# Sensor_template.net
KiCad netlist of a schematic drawn in Altium Designer
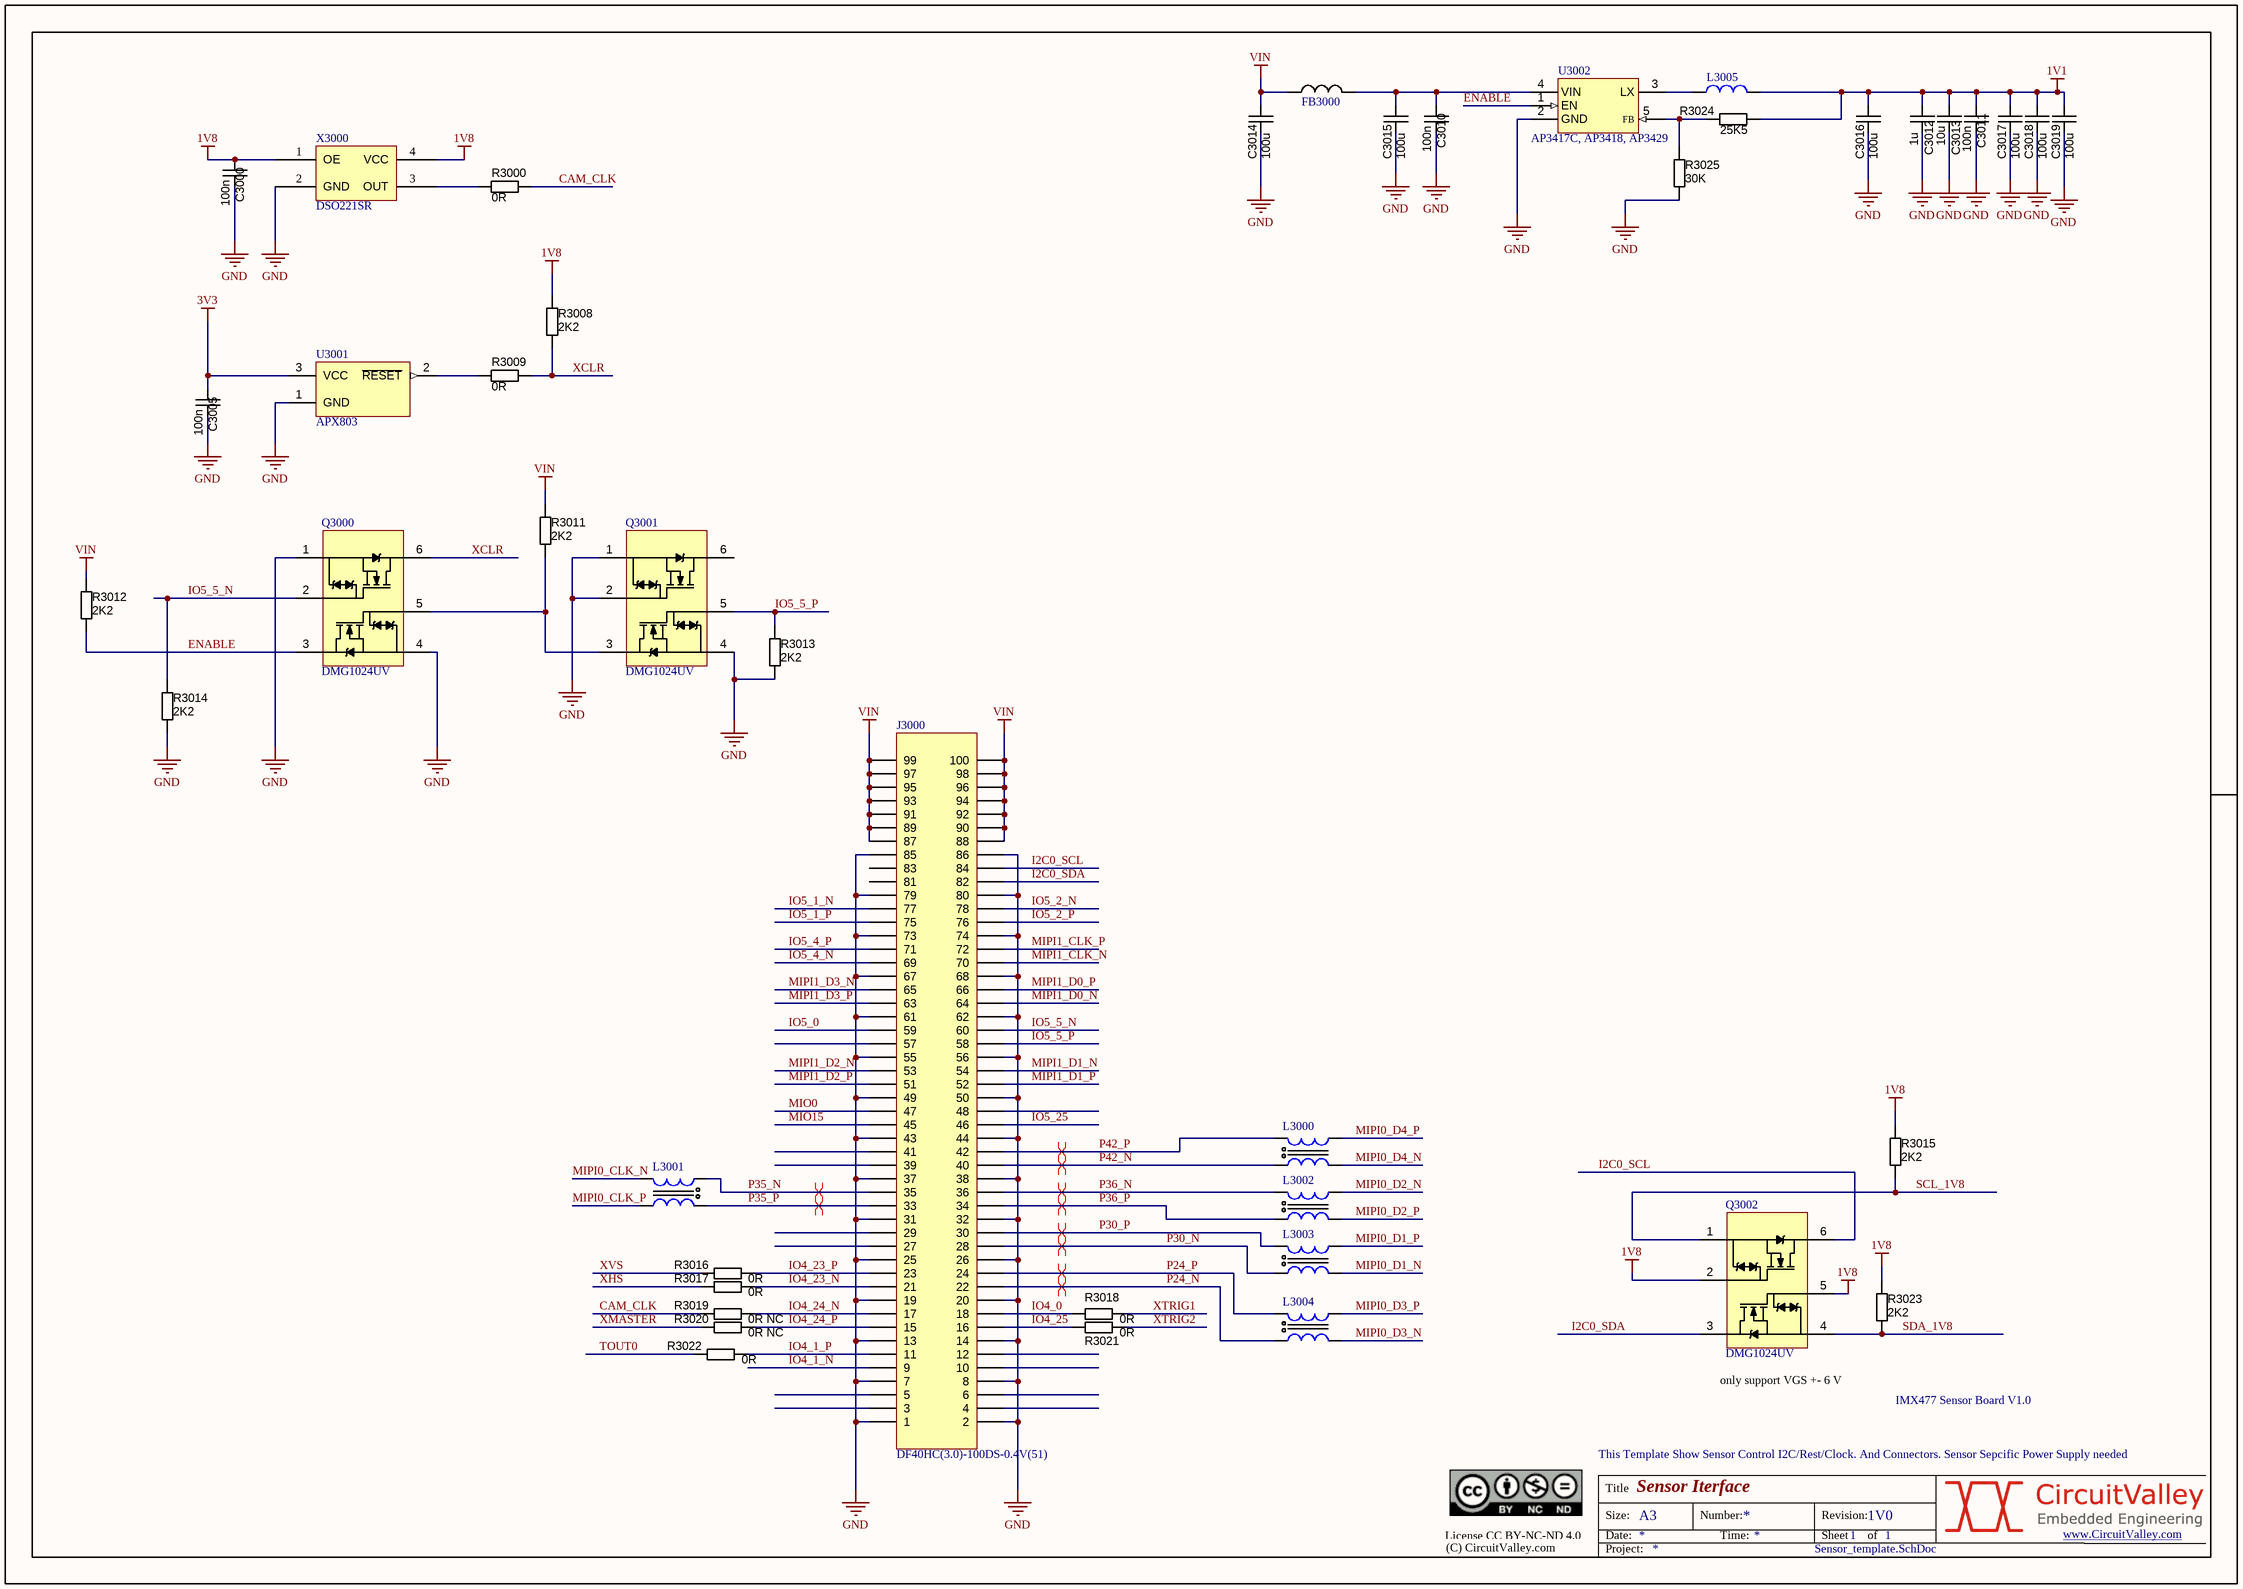
[diagram p0: Sensor_template.SchDoc]

(export (version "E")
  (design (tool "Eeschema 10.0.6"))
  (components
    (comp (ref "C3000")
      (value "100n")
      (footprint "CAPC1005N")
      (description "Capacitor SMD Cer 10nF 10% 16V X7R 0402")
      (fields (field (name "TOLERANCE") "±10%"))
      (libsource (lib "PBL - Capacitors") (part "CAPC_10n_0402_16V_10%"))
    )
    (comp (ref "C3005")
      (value "100n")
      (footprint "CAPC1005N")
      (description "Capacitor SMD Cer 10nF 10% 16V X7R 0402")
      (fields (field (name "TOLERANCE") "±10%"))
      (libsource (lib "PBL - Capacitors") (part "CAPC_10n_0402_16V_10%"))
    )
    (comp (ref "C3010")
      (value "100n")
      (footprint "CAPC1005N")
      (description "Capacitor SMD Cer 10nF 10% 16V X7R 0402")
      (fields (field (name "TOLERANCE") "±10%"))
      (libsource (lib "PBL - Capacitors") (part "CAPC_10n_0402_16V_10%"))
    )
    (comp (ref "C3011")
      (value "100n")
      (footprint "CAPC1005N")
      (description "Capacitor SMD Cer 10nF 10% 16V X7R 0402")
      (fields (field (name "TOLERANCE") "±10%"))
      (libsource (lib "PBL - Capacitors") (part "CAPC_10n_0402_16V_10%"))
    )
    (comp (ref "C3012")
      (value "1u")
      (footprint "CAPC1608N")
      (description "Capacitor SMD Cer 560pF 5% 50V NP0 0603")
      (fields (field (name "Comment") "approved sub OK"))
      (libsource (lib "PBL - Capacitors") (part "CAPC_560p_0603_5%"))
    )
    (comp (ref "C3013")
      (value "10u")
      (footprint "CAPC1608N")
      (description "Capacitor SMD Cer 560pF 5% 50V NP0 0603")
      (fields (field (name "Comment") "approved sub OK"))
      (libsource (lib "PBL - Capacitors") (part "CAPC_560p_0603_5%"))
    )
    (comp (ref "C3014")
      (value "100u")
      (footprint "CAPC2012N")
      (description "Capacitor SMD Cer 1uF 10% 16V X7R 0805")
      (fields (field (name "TOLERANCE") "±10%") (field (name "Comment") "approved sub OK"))
      (libsource (lib "PBL - Capacitors") (part "CAPC_1u_0805"))
    )
    (comp (ref "C3015")
      (value "100u")
      (footprint "CAPC2012N")
      (description "Capacitor SMD Cer 1uF 10% 16V X7R 0805")
      (fields (field (name "TOLERANCE") "±10%") (field (name "Comment") "approved sub OK"))
      (libsource (lib "PBL - Capacitors") (part "CAPC_1u_0805"))
    )
    (comp (ref "C3016")
      (value "100u")
      (footprint "CAPC2012N")
      (description "Capacitor SMD Cer 1uF 10% 16V X7R 0805")
      (fields (field (name "TOLERANCE") "±10%") (field (name "Comment") "approved sub OK"))
      (libsource (lib "PBL - Capacitors") (part "CAPC_1u_0805"))
    )
    (comp (ref "C3017")
      (value "100u")
      (footprint "CAPC2012N")
      (description "Capacitor SMD Cer 1uF 10% 16V X7R 0805")
      (fields (field (name "TOLERANCE") "±10%") (field (name "Comment") "approved sub OK"))
      (libsource (lib "PBL - Capacitors") (part "CAPC_1u_0805"))
    )
    (comp (ref "C3018")
      (value "100u")
      (footprint "CAPC2012N")
      (description "Capacitor SMD Cer 1uF 10% 16V X7R 0805")
      (fields (field (name "TOLERANCE") "±10%") (field (name "Comment") "approved sub OK"))
      (libsource (lib "PBL - Capacitors") (part "CAPC_1u_0805"))
    )
    (comp (ref "C3019")
      (value "100u")
      (footprint "CAPC2012N")
      (description "Capacitor SMD Cer 1uF 10% 16V X7R 0805")
      (fields (field (name "TOLERANCE") "±10%") (field (name "Comment") "approved sub OK"))
      (libsource (lib "PBL - Capacitors") (part "CAPC_1u_0805"))
    )
    (comp (ref "FB3000") (value "Ferrite") (footprint "INDC1608N") (libsource (lib "cvlib") (part "Ferrite")))
    (comp (ref "J3000")
      (value "DF40HC(3.0)-100DS-0.4V(51)")
      (footprint "DF40HC(3.0)-100DS-0.4V(51)")
      (description "Hiro 100 pin Connector Receptical")
      (libsource (lib "cvlib") (part "DF40HC(3.0)-100DS-0.4V(51)"))
    )
    (comp (ref "L3000")
      (value "DLM11SN900HZ2L")
      (footprint "DLM11SN900HZ2L")
      (libsource (lib "") (part "Choke_1"))
    )
    (comp (ref "L3001")
      (value "DLM11SN900HZ2L")
      (footprint "DLM11SN900HZ2L")
      (libsource (lib "cvlib") (part "Choke"))
    )
    (comp (ref "L3002")
      (value "DLM11SN900HZ2L")
      (footprint "DLM11SN900HZ2L")
      (libsource (lib "") (part "Choke_1"))
    )
    (comp (ref "L3003")
      (value "DLM11SN900HZ2L")
      (footprint "DLM11SN900HZ2L")
      (libsource (lib "") (part "Choke_1"))
    )
    (comp (ref "L3004")
      (value "DLM11SN900HZ2L")
      (footprint "DLM11SN900HZ2L")
      (libsource (lib "cvlib") (part "Choke"))
    )
    (comp (ref "L3005")
      (value "DFE252012P-2R2M=P2")
      (footprint "DFE252012P-2R2M=P2")
      (libsource (lib "cvlib") (part "inductor_smd"))
    )
    (comp (ref "Q3000") (value "DMG1024UV") (footprint "SOT563") (libsource (lib "cvlib") (part "DMG1024UV")))
    (comp (ref "Q3001") (value "DMG1024UV") (footprint "SOT563") (libsource (lib "cvlib") (part "DMG1024UV")))
    (comp (ref "Q3002") (value "DMG1024UV") (footprint "SOT563") (libsource (lib "cvlib") (part "DMG1024UV")))
    (comp (ref "R3000")
      (value "0R")
      (footprint "RESC1005N")
      (description "Resistor SMD chip 3.3k Ohm 0.063W 5% 0402")
      (fields (field (name "TOLERANCE") "±5%") (field (name "Comment") "Thick Film"))
      (libsource (lib "PBL - Resistors") (part "RES_3K3_0402_5%"))
    )
    (comp (ref "R3008")
      (value "2K2")
      (footprint "RESC1005N")
      (description "Resistor SMD chip 3.3k Ohm 0.063W 5% 0402")
      (fields (field (name "TOLERANCE") "±5%") (field (name "Comment") "Thick Film"))
      (libsource (lib "") (part "RES_3K3_0402_5%_2"))
    )
    (comp (ref "R3009")
      (value "0R")
      (footprint "RESC1005N")
      (description "Resistor SMD chip 3.3k Ohm 0.063W 5% 0402")
      (fields (field (name "TOLERANCE") "±5%") (field (name "Comment") "Thick Film"))
      (libsource (lib "PBL - Resistors") (part "RES_3K3_0402_5%"))
    )
    (comp (ref "R3011")
      (value "2K2")
      (footprint "RESC1005N")
      (description "Resistor SMD chip 3.3k Ohm 0.063W 5% 0402")
      (fields (field (name "TOLERANCE") "±5%") (field (name "Comment") "Thick Film"))
      (libsource (lib "") (part "RES_3K3_0402_5%_1"))
    )
    (comp (ref "R3012")
      (value "2K2")
      (footprint "RESC1005N")
      (description "Resistor SMD chip 3.3k Ohm 0.063W 5% 0402")
      (fields (field (name "TOLERANCE") "±5%") (field (name "Comment") "Thick Film"))
      (libsource (lib "") (part "RES_3K3_0402_5%_2"))
    )
    (comp (ref "R3013")
      (value "2K2")
      (footprint "RESC1005N")
      (description "Resistor SMD chip 3.3k Ohm 0.063W 5% 0402")
      (fields (field (name "TOLERANCE") "±5%") (field (name "Comment") "Thick Film"))
      (libsource (lib "") (part "RES_3K3_0402_5%_1"))
    )
    (comp (ref "R3014")
      (value "2K2")
      (footprint "RESC1005N")
      (description "Resistor SMD chip 3.3k Ohm 0.063W 5% 0402")
      (fields (field (name "TOLERANCE") "±5%") (field (name "Comment") "Thick Film"))
      (libsource (lib "") (part "RES_3K3_0402_5%_2"))
    )
    (comp (ref "R3015")
      (value "2K2")
      (footprint "RESC1005N")
      (description "Resistor SMD chip 3.3k Ohm 0.063W 5% 0402")
      (fields (field (name "TOLERANCE") "±5%") (field (name "Comment") "Thick Film"))
      (libsource (lib "") (part "RES_3K3_0402_5%_1"))
    )
    (comp (ref "R3016")
      (value "0R")
      (footprint "RESC1005N")
      (description "Resistor SMD chip 3.3k Ohm 0.063W 5% 0402")
      (fields (field (name "TOLERANCE") "±5%") (field (name "Comment") "Thick Film"))
      (libsource (lib "PBL - Resistors") (part "RES_3K3_0402_5%"))
    )
    (comp (ref "R3017")
      (value "0R")
      (footprint "RESC1005N")
      (description "Resistor SMD chip 3.3k Ohm 0.063W 5% 0402")
      (fields (field (name "TOLERANCE") "±5%") (field (name "Comment") "Thick Film"))
      (libsource (lib "PBL - Resistors") (part "RES_3K3_0402_5%"))
    )
    (comp (ref "R3018")
      (value "0R")
      (footprint "RESC1005N")
      (description "Resistor SMD chip 3.3k Ohm 0.063W 5% 0402")
      (fields (field (name "TOLERANCE") "±5%") (field (name "Comment") "Thick Film"))
      (libsource (lib "PBL - Resistors") (part "RES_3K3_0402_5%"))
    )
    (comp (ref "R3019")
      (value "0R NC")
      (footprint "RESC1005N")
      (description "Resistor SMD chip 3.3k Ohm 0.063W 5% 0402")
      (fields (field (name "TOLERANCE") "±5%") (field (name "Comment") "Thick Film"))
      (libsource (lib "PBL - Resistors") (part "RES_3K3_0402_5%"))
    )
    (comp (ref "R3020")
      (value "0R NC")
      (footprint "RESC1005N")
      (description "Resistor SMD chip 3.3k Ohm 0.063W 5% 0402")
      (fields (field (name "TOLERANCE") "±5%") (field (name "Comment") "Thick Film"))
      (libsource (lib "PBL - Resistors") (part "RES_3K3_0402_5%"))
    )
    (comp (ref "R3021")
      (value "0R")
      (footprint "RESC1005N")
      (description "Resistor SMD chip 3.3k Ohm 0.063W 5% 0402")
      (fields (field (name "TOLERANCE") "±5%") (field (name "Comment") "Thick Film"))
      (libsource (lib "PBL - Resistors") (part "RES_3K3_0402_5%"))
    )
    (comp (ref "R3022")
      (value "0R")
      (footprint "RESC1005N")
      (description "Resistor SMD chip 3.3k Ohm 0.063W 5% 0402")
      (fields (field (name "TOLERANCE") "±5%") (field (name "Comment") "Thick Film"))
      (libsource (lib "PBL - Resistors") (part "RES_3K3_0402_5%"))
    )
    (comp (ref "R3023")
      (value "2K2")
      (footprint "RESC1005N")
      (description "Resistor SMD chip 3.3k Ohm 0.063W 5% 0402")
      (fields (field (name "TOLERANCE") "±5%") (field (name "Comment") "Thick Film"))
      (libsource (lib "") (part "RES_3K3_0402_5%_1"))
    )
    (comp (ref "R3024")
      (value "25K5")
      (footprint "RESC1005N")
      (description "Resistor SMD chip 3.3k Ohm 0.063W 5% 0402")
      (fields (field (name "TOLERANCE") "±5%") (field (name "Comment") "Thick Film"))
      (libsource (lib "") (part "RES_3K3_0402_5%_3"))
    )
    (comp (ref "R3025")
      (value "30K")
      (footprint "RESC1005N")
      (description "Resistor SMD chip 3.3k Ohm 0.063W 5% 0402")
      (fields (field (name "TOLERANCE") "±5%") (field (name "Comment") "Thick Film"))
      (libsource (lib "") (part "RES_3K3_0402_5%_1"))
    )
    (comp (ref "U3001") (value "APX803") (footprint "SOT23-3") (libsource (lib "cvlib") (part "APX803")))
    (comp (ref "U3002")
      (value "AP3417C, AP3418, AP3429")
      (footprint "SOT23-5")
      (libsource (lib "cvlib") (part "AP3417C"))
    )
    (comp (ref "X3000")
      (value "DSO221SR")
      (footprint "Active Oscillator 2520")
      (description "Active Oscillator_2520")
      (libsource (lib "Crystal_and_oscillator") (part "Oscillator_2520"))
    )
  )
  (nets
    (net (code "1") (name "/CAM_CLK") (class "Default")
      (node (ref "R3000") (pin "1") (pinfunction "1_1") (pintype "passive"))
      (node (ref "R3019") (pin "2") (pinfunction "2_2") (pintype "passive"))
    )
    (net (code "2") (name "/ENABLE") (class "Default")
      (node (ref "Q3000") (pin "3") (pinfunction "D_3") (pintype "passive"))
      (node (ref "R3012") (pin "2") (pinfunction "2_2") (pintype "passive"))
      (node (ref "U3002") (pin "1") (pinfunction "EN_1") (pintype "input"))
    )
    (net (code "3") (name "/I2C0_SCL") (class "Default")
      (node (ref "J3000") (pin "84") (pinfunction "84_84") (pintype "passive"))
      (node (ref "Q3002") (pin "6") (pinfunction "D_6") (pintype "passive"))
    )
    (net (code "4") (name "/I2C0_SDA") (class "Default")
      (node (ref "J3000") (pin "82") (pinfunction "82_82") (pintype "passive"))
      (node (ref "Q3002") (pin "3") (pinfunction "D_3") (pintype "passive"))
    )
    (net (code "5") (name "/IO4_0") (class "Default")
      (node (ref "J3000") (pin "18") (pinfunction "18_18") (pintype "passive"))
      (node (ref "R3018") (pin "2") (pinfunction "2_2") (pintype "passive"))
    )
    (net (code "6") (name "/IO4_1_N") (class "Default")
      (node (ref "J3000") (pin "9") (pinfunction "9_9") (pintype "passive"))
    )
    (net (code "7") (name "/IO4_1_P") (class "Default")
      (node (ref "J3000") (pin "11") (pinfunction "11_11") (pintype "passive"))
      (node (ref "R3022") (pin "1") (pinfunction "1_1") (pintype "passive"))
    )
    (net (code "8") (name "/IO4_23_N") (class "Default")
      (node (ref "J3000") (pin "21") (pinfunction "21_21") (pintype "passive"))
      (node (ref "R3017") (pin "1") (pinfunction "1_1") (pintype "passive"))
    )
    (net (code "9") (name "/IO4_23_P") (class "Default")
      (node (ref "J3000") (pin "23") (pinfunction "23_23") (pintype "passive"))
      (node (ref "R3016") (pin "1") (pinfunction "1_1") (pintype "passive"))
    )
    (net (code "10") (name "/IO4_24_N") (class "Default")
      (node (ref "J3000") (pin "17") (pinfunction "17_17") (pintype "passive"))
      (node (ref "R3019") (pin "1") (pinfunction "1_1") (pintype "passive"))
    )
    (net (code "11") (name "/IO4_24_P") (class "Default")
      (node (ref "J3000") (pin "15") (pinfunction "15_15") (pintype "passive"))
      (node (ref "R3020") (pin "1") (pinfunction "1_1") (pintype "passive"))
    )
    (net (code "12") (name "/IO4_25") (class "Default")
      (node (ref "J3000") (pin "16") (pinfunction "16_16") (pintype "passive"))
      (node (ref "R3021") (pin "2") (pinfunction "2_2") (pintype "passive"))
    )
    (net (code "13") (name "/IO5_0") (class "Default")
      (node (ref "J3000") (pin "59") (pinfunction "59_59") (pintype "passive"))
    )
    (net (code "14") (name "/IO5_1_N") (class "Default")
      (node (ref "J3000") (pin "77") (pinfunction "77_77") (pintype "passive"))
    )
    (net (code "15") (name "/IO5_1_P") (class "Default")
      (node (ref "J3000") (pin "75") (pinfunction "75_75") (pintype "passive"))
    )
    (net (code "16") (name "/IO5_2_N") (class "Default")
      (node (ref "J3000") (pin "78") (pinfunction "78_78") (pintype "passive"))
    )
    (net (code "17") (name "/IO5_2_P") (class "Default")
      (node (ref "J3000") (pin "76") (pinfunction "76_76") (pintype "passive"))
    )
    (net (code "18") (name "/IO5_4_N") (class "Default")
      (node (ref "J3000") (pin "69") (pinfunction "69_69") (pintype "passive"))
    )
    (net (code "19") (name "/IO5_4_P") (class "Default")
      (node (ref "J3000") (pin "71") (pinfunction "71_71") (pintype "passive"))
    )
    (net (code "20") (name "/IO5_5_N") (class "Default")
      (node (ref "J3000") (pin "60") (pinfunction "60_60") (pintype "passive"))
      (node (ref "Q3000") (pin "2") (pinfunction "G_2") (pintype "passive"))
      (node (ref "R3014") (pin "1") (pinfunction "1_1") (pintype "passive"))
    )
    (net (code "21") (name "/IO5_5_P") (class "Default")
      (node (ref "J3000") (pin "58") (pinfunction "58_58") (pintype "passive"))
      (node (ref "Q3001") (pin "5") (pinfunction "G_5") (pintype "passive"))
      (node (ref "R3013") (pin "2") (pinfunction "2_2") (pintype "passive"))
    )
    (net (code "22") (name "/IO5_25") (class "Default")
      (node (ref "J3000") (pin "46") (pinfunction "46_46") (pintype "passive"))
    )
    (net (code "23") (name "/MIO0") (class "Default")
      (node (ref "J3000") (pin "47") (pinfunction "47_47") (pintype "passive"))
    )
    (net (code "24") (name "/MIO15") (class "Default")
      (node (ref "J3000") (pin "45") (pinfunction "45_45") (pintype "passive"))
    )
    (net (code "25") (name "/MIPI0_CLK_N") (class "Default")
      (node (ref "L3001") (pin "3") (pinfunction "3_3") (pintype "passive"))
    )
    (net (code "26") (name "/MIPI0_CLK_P") (class "Default")
      (node (ref "L3001") (pin "2") (pinfunction "2_2") (pintype "passive"))
    )
    (net (code "27") (name "/MIPI0_D1_N") (class "Default")
      (node (ref "L3003") (pin "2") (pinfunction "2_2") (pintype "passive"))
    )
    (net (code "28") (name "/MIPI0_D1_P") (class "Default")
      (node (ref "L3003") (pin "3") (pinfunction "3_3") (pintype "passive"))
    )
    (net (code "29") (name "/MIPI0_D2_N") (class "Default")
      (node (ref "L3002") (pin "3") (pinfunction "3_3") (pintype "passive"))
    )
    (net (code "30") (name "/MIPI0_D2_P") (class "Default")
      (node (ref "L3002") (pin "2") (pinfunction "2_2") (pintype "passive"))
    )
    (net (code "31") (name "/MIPI0_D3_N") (class "Default")
      (node (ref "L3004") (pin "3") (pinfunction "3_3") (pintype "passive"))
    )
    (net (code "32") (name "/MIPI0_D3_P") (class "Default")
      (node (ref "L3004") (pin "2") (pinfunction "2_2") (pintype "passive"))
    )
    (net (code "33") (name "/MIPI0_D4_N") (class "Default")
      (node (ref "L3000") (pin "2") (pinfunction "2_2") (pintype "passive"))
    )
    (net (code "34") (name "/MIPI0_D4_P") (class "Default")
      (node (ref "L3000") (pin "3") (pinfunction "3_3") (pintype "passive"))
    )
    (net (code "35") (name "/MIPI1_CLK_N") (class "Default")
      (node (ref "J3000") (pin "70") (pinfunction "70_70") (pintype "passive"))
    )
    (net (code "36") (name "/MIPI1_CLK_P") (class "Default")
      (node (ref "J3000") (pin "72") (pinfunction "72_72") (pintype "passive"))
    )
    (net (code "37") (name "/MIPI1_D0_N") (class "Default")
      (node (ref "J3000") (pin "64") (pinfunction "64_64") (pintype "passive"))
    )
    (net (code "38") (name "/MIPI1_D0_P") (class "Default")
      (node (ref "J3000") (pin "66") (pinfunction "66_66") (pintype "passive"))
    )
    (net (code "39") (name "/MIPI1_D1_N") (class "Default")
      (node (ref "J3000") (pin "54") (pinfunction "54_54") (pintype "passive"))
    )
    (net (code "40") (name "/MIPI1_D1_P") (class "Default")
      (node (ref "J3000") (pin "52") (pinfunction "52_52") (pintype "passive"))
    )
    (net (code "41") (name "/MIPI1_D2_N") (class "Default")
      (node (ref "J3000") (pin "53") (pinfunction "53_53") (pintype "passive"))
    )
    (net (code "42") (name "/MIPI1_D2_P") (class "Default")
      (node (ref "J3000") (pin "51") (pinfunction "51_51") (pintype "passive"))
    )
    (net (code "43") (name "/MIPI1_D3_N") (class "Default")
      (node (ref "J3000") (pin "65") (pinfunction "65_65") (pintype "passive"))
    )
    (net (code "44") (name "/MIPI1_D3_P") (class "Default")
      (node (ref "J3000") (pin "63") (pinfunction "63_63") (pintype "passive"))
    )
    (net (code "45") (name "/P24_N") (class "Default")
      (node (ref "J3000") (pin "22") (pinfunction "22_22") (pintype "passive"))
      (node (ref "L3004") (pin "4") (pinfunction "4_4") (pintype "passive"))
    )
    (net (code "46") (name "/P24_P") (class "Default")
      (node (ref "J3000") (pin "24") (pinfunction "24_24") (pintype "passive"))
      (node (ref "L3004") (pin "1") (pinfunction "1_1") (pintype "passive"))
    )
    (net (code "47") (name "/P30_N") (class "Default")
      (node (ref "J3000") (pin "28") (pinfunction "28_28") (pintype "passive"))
      (node (ref "L3003") (pin "1") (pinfunction "1_1") (pintype "passive"))
    )
    (net (code "48") (name "/P30_P") (class "Default")
      (node (ref "J3000") (pin "30") (pinfunction "30_30") (pintype "passive"))
      (node (ref "L3003") (pin "4") (pinfunction "4_4") (pintype "passive"))
    )
    (net (code "49") (name "/P35_N") (class "Default")
      (node (ref "J3000") (pin "35") (pinfunction "35_35") (pintype "passive"))
      (node (ref "L3001") (pin "4") (pinfunction "4_4") (pintype "passive"))
    )
    (net (code "50") (name "/P35_P") (class "Default")
      (node (ref "J3000") (pin "33") (pinfunction "33_33") (pintype "passive"))
      (node (ref "L3001") (pin "1") (pinfunction "1_1") (pintype "passive"))
    )
    (net (code "51") (name "/P36_N") (class "Default")
      (node (ref "J3000") (pin "36") (pinfunction "36_36") (pintype "passive"))
      (node (ref "L3002") (pin "4") (pinfunction "4_4") (pintype "passive"))
    )
    (net (code "52") (name "/P36_P") (class "Default")
      (node (ref "J3000") (pin "34") (pinfunction "34_34") (pintype "passive"))
      (node (ref "L3002") (pin "1") (pinfunction "1_1") (pintype "passive"))
    )
    (net (code "53") (name "/P42_N") (class "Default")
      (node (ref "J3000") (pin "40") (pinfunction "40_40") (pintype "passive"))
      (node (ref "L3000") (pin "1") (pinfunction "1_1") (pintype "passive"))
    )
    (net (code "54") (name "/P42_P") (class "Default")
      (node (ref "J3000") (pin "42") (pinfunction "42_42") (pintype "passive"))
      (node (ref "L3000") (pin "4") (pinfunction "4_4") (pintype "passive"))
    )
    (net (code "55") (name "/SCL_1V8") (class "Default")
      (node (ref "Q3002") (pin "1") (pinfunction "S_1") (pintype "passive"))
      (node (ref "R3015") (pin "1") (pinfunction "1_1") (pintype "passive"))
    )
    (net (code "56") (name "/SDA_1V8") (class "Default")
      (node (ref "Q3002") (pin "4") (pinfunction "S_4") (pintype "passive"))
      (node (ref "R3023") (pin "1") (pinfunction "1_1") (pintype "passive"))
    )
    (net (code "57") (name "/TOUT0") (class "Default")
      (node (ref "R3022") (pin "2") (pinfunction "2_2") (pintype "passive"))
    )
    (net (code "58") (name "/XCLR") (class "Default")
      (node (ref "Q3000") (pin "6") (pinfunction "D_6") (pintype "passive"))
      (node (ref "R3008") (pin "2") (pinfunction "2_2") (pintype "passive"))
      (node (ref "R3009") (pin "1") (pinfunction "1_1") (pintype "passive"))
    )
    (net (code "59") (name "/XHS") (class "Default")
      (node (ref "R3017") (pin "2") (pinfunction "2_2") (pintype "passive"))
    )
    (net (code "60") (name "/XMASTER") (class "Default")
      (node (ref "R3020") (pin "2") (pinfunction "2_2") (pintype "passive"))
    )
    (net (code "61") (name "/XTRIG1") (class "Default")
      (node (ref "R3018") (pin "1") (pinfunction "1_1") (pintype "passive"))
    )
    (net (code "62") (name "/XTRIG2") (class "Default")
      (node (ref "R3021") (pin "1") (pinfunction "1_1") (pintype "passive"))
    )
    (net (code "63") (name "/XVS") (class "Default")
      (node (ref "R3016") (pin "2") (pinfunction "2_2") (pintype "passive"))
    )
    (net (code "64") (name "1V1") (class "Default")
      (node (ref "C3011") (pin "2") (pintype "passive"))
      (node (ref "C3012") (pin "1") (pintype "passive"))
      (node (ref "C3013") (pin "1") (pintype "passive"))
      (node (ref "C3016") (pin "1") (pintype "passive"))
      (node (ref "C3017") (pin "1") (pintype "passive"))
      (node (ref "C3018") (pin "1") (pintype "passive"))
      (node (ref "C3019") (pin "1") (pintype "passive"))
      (node (ref "L3005") (pin "2") (pinfunction "2_2") (pintype "passive"))
      (node (ref "R3024") (pin "2") (pinfunction "2_2") (pintype "passive"))
    )
    (net (code "65") (name "1V8") (class "Default")
      (node (ref "C3000") (pin "2") (pintype "passive"))
      (node (ref "Q3002") (pin "2") (pinfunction "G_2") (pintype "passive"))
      (node (ref "Q3002") (pin "5") (pinfunction "G_5") (pintype "passive"))
      (node (ref "R3008") (pin "1") (pinfunction "1_1") (pintype "passive"))
      (node (ref "R3015") (pin "2") (pinfunction "2_2") (pintype "passive"))
      (node (ref "R3023") (pin "2") (pinfunction "2_2") (pintype "passive"))
      (node (ref "X3000") (pin "1") (pinfunction "OE_1") (pintype "passive"))
      (node (ref "X3000") (pin "4") (pinfunction "VCC_4") (pintype "passive"))
    )
    (net (code "66") (name "3V3") (class "Default")
      (node (ref "C3005") (pin "2") (pintype "passive"))
      (node (ref "U3001") (pin "3") (pinfunction "VCC_3") (pintype "power_in"))
    )
    (net (code "67") (name "GND") (class "Default")
      (node (ref "C3000") (pin "1") (pintype "passive"))
      (node (ref "C3005") (pin "1") (pintype "passive"))
      (node (ref "C3010") (pin "1") (pintype "passive"))
      (node (ref "C3011") (pin "1") (pintype "passive"))
      (node (ref "C3012") (pin "2") (pintype "passive"))
      (node (ref "C3013") (pin "2") (pintype "passive"))
      (node (ref "C3014") (pin "2") (pintype "passive"))
      (node (ref "C3015") (pin "2") (pintype "passive"))
      (node (ref "C3016") (pin "2") (pintype "passive"))
      (node (ref "C3017") (pin "2") (pintype "passive"))
      (node (ref "C3018") (pin "2") (pintype "passive"))
      (node (ref "C3019") (pin "2") (pintype "passive"))
      (node (ref "J3000") (pin "1") (pinfunction "1_1") (pintype "passive"))
      (node (ref "J3000") (pin "13") (pinfunction "13_13") (pintype "passive"))
      (node (ref "J3000") (pin "14") (pinfunction "14_14") (pintype "passive"))
      (node (ref "J3000") (pin "19") (pinfunction "19_19") (pintype "passive"))
      (node (ref "J3000") (pin "2") (pinfunction "2_2") (pintype "passive"))
      (node (ref "J3000") (pin "20") (pinfunction "20_20") (pintype "passive"))
      (node (ref "J3000") (pin "25") (pinfunction "25_25") (pintype "passive"))
      (node (ref "J3000") (pin "26") (pinfunction "26_26") (pintype "passive"))
      (node (ref "J3000") (pin "31") (pinfunction "31_31") (pintype "passive"))
      (node (ref "J3000") (pin "32") (pinfunction "32_32") (pintype "passive"))
      (node (ref "J3000") (pin "37") (pinfunction "37_37") (pintype "passive"))
      (node (ref "J3000") (pin "38") (pinfunction "38_38") (pintype "passive"))
      (node (ref "J3000") (pin "43") (pinfunction "43_43") (pintype "passive"))
      (node (ref "J3000") (pin "44") (pinfunction "44_44") (pintype "passive"))
      (node (ref "J3000") (pin "49") (pinfunction "49_49") (pintype "passive"))
      (node (ref "J3000") (pin "50") (pinfunction "50_50") (pintype "passive"))
      (node (ref "J3000") (pin "55") (pinfunction "55_55") (pintype "passive"))
      (node (ref "J3000") (pin "56") (pinfunction "56_56") (pintype "passive"))
      (node (ref "J3000") (pin "61") (pinfunction "61_61") (pintype "passive"))
      (node (ref "J3000") (pin "62") (pinfunction "62_62") (pintype "passive"))
      (node (ref "J3000") (pin "67") (pinfunction "67_67") (pintype "passive"))
      (node (ref "J3000") (pin "68") (pinfunction "68_68") (pintype "passive"))
      (node (ref "J3000") (pin "7") (pinfunction "7_7") (pintype "passive"))
      (node (ref "J3000") (pin "73") (pinfunction "73_73") (pintype "passive"))
      (node (ref "J3000") (pin "74") (pinfunction "74_74") (pintype "passive"))
      (node (ref "J3000") (pin "79") (pinfunction "79_79") (pintype "passive"))
      (node (ref "J3000") (pin "8") (pinfunction "8_8") (pintype "passive"))
      (node (ref "J3000") (pin "80") (pinfunction "80_80") (pintype "passive"))
      (node (ref "J3000") (pin "85") (pinfunction "85_85") (pintype "passive"))
      (node (ref "J3000") (pin "86") (pinfunction "86_86") (pintype "passive"))
      (node (ref "Q3000") (pin "1") (pinfunction "S_1") (pintype "passive"))
      (node (ref "Q3000") (pin "4") (pinfunction "S_4") (pintype "passive"))
      (node (ref "Q3001") (pin "1") (pinfunction "S_1") (pintype "passive"))
      (node (ref "Q3001") (pin "2") (pinfunction "G_2") (pintype "passive"))
      (node (ref "Q3001") (pin "4") (pinfunction "S_4") (pintype "passive"))
      (node (ref "R3013") (pin "1") (pinfunction "1_1") (pintype "passive"))
      (node (ref "R3014") (pin "2") (pinfunction "2_2") (pintype "passive"))
      (node (ref "R3025") (pin "1") (pinfunction "1_1") (pintype "passive"))
      (node (ref "U3001") (pin "1") (pinfunction "GND_1") (pintype "power_in"))
      (node (ref "U3002") (pin "2") (pinfunction "GND_2") (pintype "power_in"))
      (node (ref "X3000") (pin "2") (pinfunction "GND_2") (pintype "passive"))
    )
    (net (code "68") (name "Net-(Q3000-G-Pad5)") (class "Default")
      (node (ref "Q3000") (pin "5") (pinfunction "G_5") (pintype "passive"))
      (node (ref "Q3001") (pin "3") (pinfunction "D_3") (pintype "passive"))
      (node (ref "R3011") (pin "1") (pinfunction "1_1") (pintype "passive"))
    )
    (net (code "69") (name "Net-(U3001-~{RESET})") (class "Default")
      (node (ref "R3009") (pin "2") (pinfunction "2_2") (pintype "passive"))
      (node (ref "U3001") (pin "2") (pinfunction "~{RESET}_2") (pintype "output"))
    )
    (net (code "70") (name "Net-(U3002-FB)") (class "Default")
      (node (ref "R3024") (pin "1") (pinfunction "1_1") (pintype "passive"))
      (node (ref "R3025") (pin "2") (pinfunction "2_2") (pintype "passive"))
      (node (ref "U3002") (pin "5") (pinfunction "FB_5") (pintype "input"))
    )
    (net (code "71") (name "Net-(U3002-LX)") (class "Default")
      (node (ref "L3005") (pin "1") (pinfunction "1_1") (pintype "passive"))
      (node (ref "U3002") (pin "3") (pinfunction "LX_3") (pintype "passive"))
    )
    (net (code "72") (name "Net-(U3002-VIN)") (class "Default")
      (node (ref "C3010") (pin "2") (pintype "passive"))
      (node (ref "C3015") (pin "1") (pintype "passive"))
      (node (ref "FB3000") (pin "2") (pinfunction "2_2") (pintype "passive"))
      (node (ref "U3002") (pin "4") (pinfunction "VIN_4") (pintype "power_in"))
    )
    (net (code "73") (name "Net-(X3000-OUT)") (class "Default")
      (node (ref "R3000") (pin "2") (pinfunction "2_2") (pintype "passive"))
      (node (ref "X3000") (pin "3") (pinfunction "OUT_3") (pintype "passive"))
    )
    (net (code "74") (name "VIN") (class "Default")
      (node (ref "C3014") (pin "1") (pintype "passive"))
      (node (ref "FB3000") (pin "1") (pinfunction "1_1") (pintype "passive"))
      (node (ref "J3000") (pin "100") (pinfunction "100_100") (pintype "passive"))
      (node (ref "J3000") (pin "87") (pinfunction "87_87") (pintype "passive"))
      (node (ref "J3000") (pin "88") (pinfunction "88_88") (pintype "passive"))
      (node (ref "J3000") (pin "89") (pinfunction "89_89") (pintype "passive"))
      (node (ref "J3000") (pin "90") (pinfunction "90_90") (pintype "passive"))
      (node (ref "J3000") (pin "91") (pinfunction "91_91") (pintype "passive"))
      (node (ref "J3000") (pin "92") (pinfunction "92_92") (pintype "passive"))
      (node (ref "J3000") (pin "93") (pinfunction "93_93") (pintype "passive"))
      (node (ref "J3000") (pin "94") (pinfunction "94_94") (pintype "passive"))
      (node (ref "J3000") (pin "95") (pinfunction "95_95") (pintype "passive"))
      (node (ref "J3000") (pin "96") (pinfunction "96_96") (pintype "passive"))
      (node (ref "J3000") (pin "97") (pinfunction "97_97") (pintype "passive"))
      (node (ref "J3000") (pin "98") (pinfunction "98_98") (pintype "passive"))
      (node (ref "J3000") (pin "99") (pinfunction "99_99") (pintype "passive"))
      (node (ref "R3011") (pin "2") (pinfunction "2_2") (pintype "passive"))
      (node (ref "R3012") (pin "1") (pinfunction "1_1") (pintype "passive"))
    )
    (net (code "75") (name "unconnected-(J3000-Pad3)") (class "Default")
      (node (ref "J3000") (pin "3") (pinfunction "3_3") (pintype "passive"))
    )
    (net (code "76") (name "unconnected-(J3000-Pad4)") (class "Default")
      (node (ref "J3000") (pin "4") (pinfunction "4_4") (pintype "passive"))
    )
    (net (code "77") (name "unconnected-(J3000-Pad5)") (class "Default")
      (node (ref "J3000") (pin "5") (pinfunction "5_5") (pintype "passive"))
    )
    (net (code "78") (name "unconnected-(J3000-Pad6)") (class "Default")
      (node (ref "J3000") (pin "6") (pinfunction "6_6") (pintype "passive"))
    )
    (net (code "79") (name "unconnected-(J3000-Pad10)") (class "Default")
      (node (ref "J3000") (pin "10") (pinfunction "10_10") (pintype "passive"))
    )
    (net (code "80") (name "unconnected-(J3000-Pad12)") (class "Default")
      (node (ref "J3000") (pin "12") (pinfunction "12_12") (pintype "passive"))
    )
    (net (code "81") (name "unconnected-(J3000-Pad27)") (class "Default")
      (node (ref "J3000") (pin "27") (pinfunction "27_27") (pintype "passive"))
    )
    (net (code "82") (name "unconnected-(J3000-Pad29)") (class "Default")
      (node (ref "J3000") (pin "29") (pinfunction "29_29") (pintype "passive"))
    )
    (net (code "83") (name "unconnected-(J3000-Pad39)") (class "Default")
      (node (ref "J3000") (pin "39") (pinfunction "39_39") (pintype "passive"))
    )
    (net (code "84") (name "unconnected-(J3000-Pad41)") (class "Default")
      (node (ref "J3000") (pin "41") (pinfunction "41_41") (pintype "passive"))
    )
    (net (code "85") (name "unconnected-(J3000-Pad48)") (class "Default")
      (node (ref "J3000") (pin "48") (pinfunction "48_48") (pintype "passive"))
    )
    (net (code "86") (name "unconnected-(J3000-Pad57)") (class "Default")
      (node (ref "J3000") (pin "57") (pinfunction "57_57") (pintype "passive"))
    )
    (net (code "87") (name "unconnected-(J3000-Pad81)") (class "Default")
      (node (ref "J3000") (pin "81") (pinfunction "81_81") (pintype "passive"))
    )
    (net (code "88") (name "unconnected-(J3000-Pad83)") (class "Default")
      (node (ref "J3000") (pin "83") (pinfunction "83_83") (pintype "passive"))
    )
    (net (code "89") (name "unconnected-(Q3001-D-Pad6)") (class "Default")
      (node (ref "Q3001") (pin "6") (pinfunction "D_6") (pintype "passive"))
    )
  )
)
